# motor_driver.net
KiCad netlist of a schematic drawn in Altium Designer
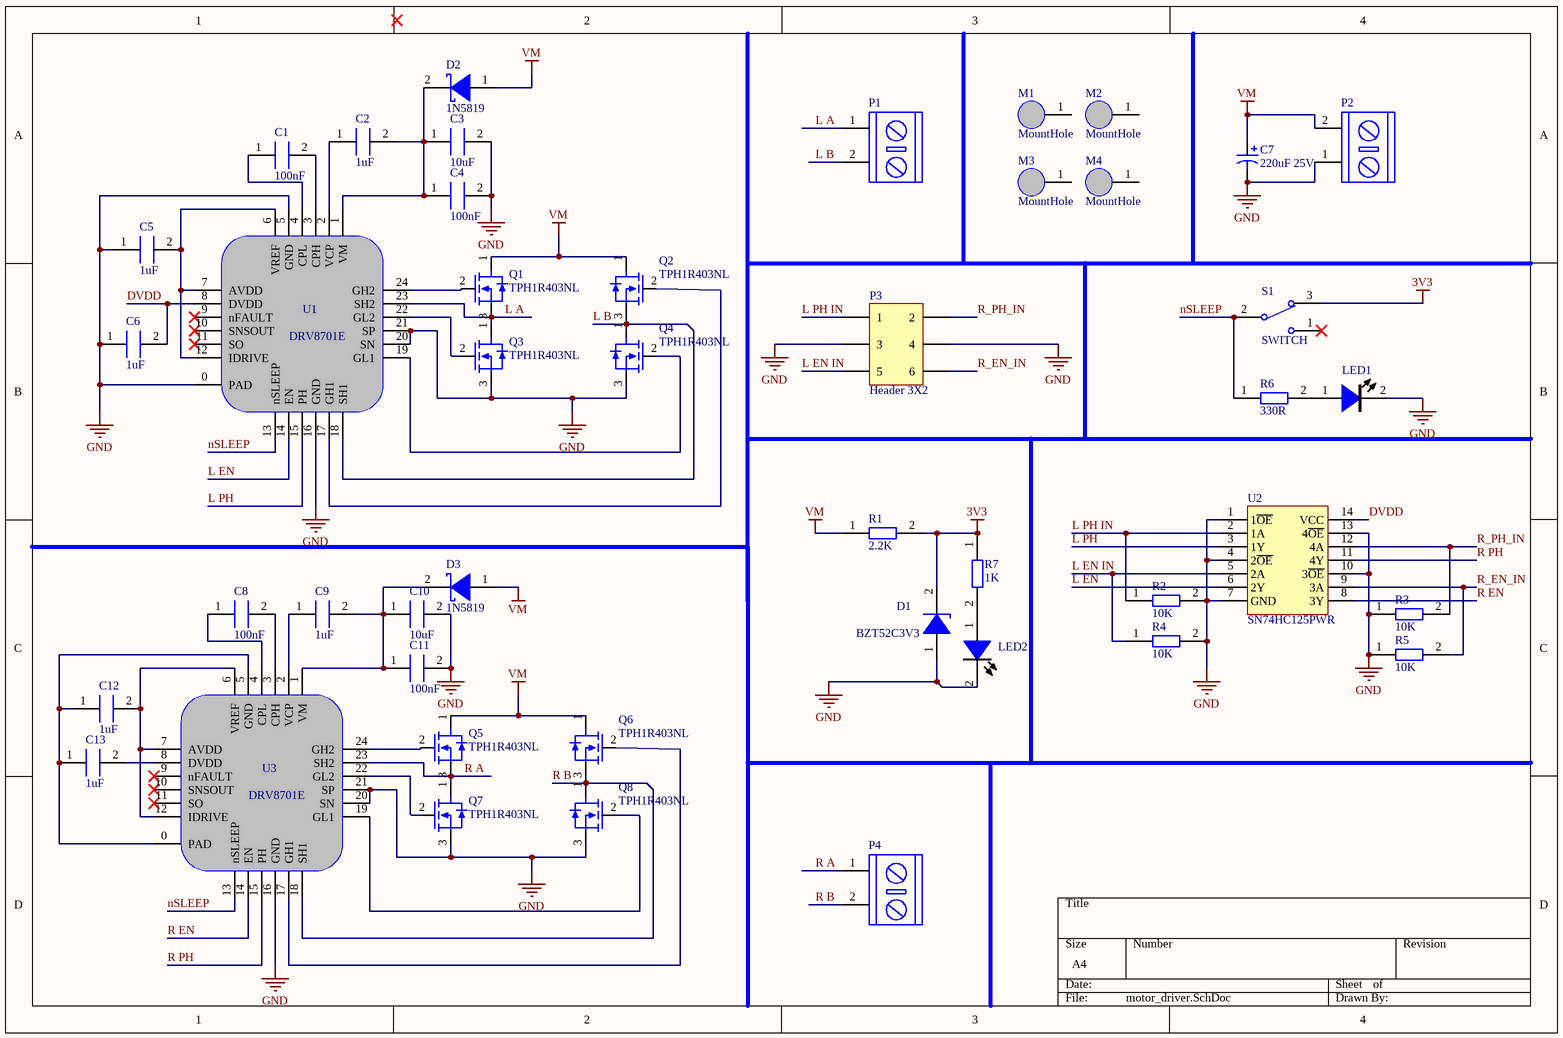
[diagram p0: motor_driver.SchDoc]

(export (version "E")
  (design (tool "Eeschema 10.0.6"))
  (components
    (comp (ref "C1")
      (value "100nF")
      (footprint "C0603")
      (description "电容")
      (libsource (lib "Learning") (part "CAP"))
    )
    (comp (ref "C2")
      (value "1uF")
      (footprint "C0603")
      (description "电容")
      (libsource (lib "Learning") (part "CAP"))
    )
    (comp (ref "C3")
      (value "10uF")
      (footprint "C0805")
      (description "电容")
      (libsource (lib "Learning") (part "CAP"))
    )
    (comp (ref "C4")
      (value "100nF")
      (footprint "C0603")
      (description "电容")
      (libsource (lib "Learning") (part "CAP"))
    )
    (comp (ref "C5")
      (value "1uF")
      (footprint "C0603")
      (description "电容")
      (libsource (lib "Learning") (part "CAP"))
    )
    (comp (ref "C6")
      (value "1uF")
      (footprint "C0603")
      (description "电容")
      (libsource (lib "Learning") (part "CAP"))
    )
    (comp (ref "C7") (value "220uF 25V") (footprint "RB.2/.4") (libsource (lib "Learning") (part "CAP_2")))
    (comp (ref "C8")
      (value "100nF")
      (footprint "C0603")
      (description "电容")
      (libsource (lib "Learning") (part "CAP"))
    )
    (comp (ref "C9")
      (value "1uF")
      (footprint "C0603")
      (description "电容")
      (libsource (lib "Learning") (part "CAP"))
    )
    (comp (ref "C10")
      (value "10uF")
      (footprint "C0805")
      (description "电容")
      (libsource (lib "Learning") (part "CAP"))
    )
    (comp (ref "C11")
      (value "100nF")
      (footprint "C0603")
      (description "电容")
      (libsource (lib "Learning") (part "CAP"))
    )
    (comp (ref "C12")
      (value "1uF")
      (footprint "C0603")
      (description "电容")
      (libsource (lib "Learning") (part "CAP"))
    )
    (comp (ref "C13")
      (value "1uF")
      (footprint "C0603")
      (description "电容")
      (libsource (lib "Learning") (part "CAP"))
    )
    (comp (ref "D1")
      (value "BZT52C3V3")
      (footprint "SOD-123")
      (libsource (lib "Learning") (part "BZT52C3V3"))
    )
    (comp (ref "D2") (value "1N5819") (footprint "SOD-123") (libsource (lib "Learning") (part "1N5819")))
    (comp (ref "D3") (value "1N5819") (footprint "SOD-123") (libsource (lib "Learning") (part "1N5819")))
    (comp (ref "LED1") (value "LED") (footprint "LED-0805") (libsource (lib "Learning") (part "LED")))
    (comp (ref "LED2") (value "LED") (footprint "LED-0805") (libsource (lib "Learning") (part "LED")))
    (comp (ref "M1")
      (value "MountHole")
      (footprint "MountHole")
      (libsource (lib "Learning") (part "MountHole"))
    )
    (comp (ref "M2")
      (value "MountHole")
      (footprint "MountHole")
      (libsource (lib "Learning") (part "MountHole"))
    )
    (comp (ref "M3")
      (value "MountHole")
      (footprint "MountHole")
      (libsource (lib "Learning") (part "MountHole"))
    )
    (comp (ref "M4")
      (value "MountHole")
      (footprint "MountHole")
      (libsource (lib "Learning") (part "MountHole"))
    )
    (comp (ref "P1")
      (value "接口_1")
      (footprint "KF/WJ/DG 301-2p-5.0mm")
      (libsource (lib "Learning") (part "接口_1"))
    )
    (comp (ref "P2")
      (value "接口")
      (footprint "KF/WJ/DG 301-2p-5.0mm")
      (libsource (lib "Learning") (part "接口"))
    )
    (comp (ref "P3")
      (value "Header 3X2")
      (footprint "PIN-2x3-2.54-1.0")
      (libsource (lib "Learning") (part "Header 3X2"))
    )
    (comp (ref "P4")
      (value "接口_1")
      (footprint "KF/WJ/DG 301-2p-5.0mm")
      (libsource (lib "Learning") (part "接口_1"))
    )
    (comp (ref "Q1")
      (value "TPH1R403NL")
      (footprint "DFN5x6")
      (description "MOSFET")
      (libsource (lib "Learning") (part "TPH1R403NL"))
    )
    (comp (ref "Q2")
      (value "TPH1R403NL")
      (footprint "DFN5x6")
      (description "MOSFET")
      (libsource (lib "Learning") (part "TPH1R403NL"))
    )
    (comp (ref "Q3")
      (value "TPH1R403NL")
      (footprint "DFN5x6")
      (description "MOSFET")
      (libsource (lib "Learning") (part "TPH1R403NL"))
    )
    (comp (ref "Q4")
      (value "TPH1R403NL")
      (footprint "DFN5x6")
      (description "MOSFET")
      (libsource (lib "Learning") (part "TPH1R403NL"))
    )
    (comp (ref "Q5")
      (value "TPH1R403NL")
      (footprint "DFN5x6")
      (description "MOSFET")
      (libsource (lib "Learning") (part "TPH1R403NL"))
    )
    (comp (ref "Q6")
      (value "TPH1R403NL")
      (footprint "DFN5x6")
      (description "MOSFET")
      (libsource (lib "Learning") (part "TPH1R403NL"))
    )
    (comp (ref "Q7")
      (value "TPH1R403NL")
      (footprint "DFN5x6")
      (description "MOSFET")
      (libsource (lib "Learning") (part "TPH1R403NL"))
    )
    (comp (ref "Q8")
      (value "TPH1R403NL")
      (footprint "DFN5x6")
      (description "MOSFET")
      (libsource (lib "Learning") (part "TPH1R403NL"))
    )
    (comp (ref "R1")
      (value "2.2K")
      (footprint "0603")
      (description "电阻")
      (libsource (lib "Learning") (part "RES"))
    )
    (comp (ref "R2")
      (value "10K")
      (footprint "0603")
      (description "电阻")
      (libsource (lib "Learning") (part "RES"))
    )
    (comp (ref "R3")
      (value "10K")
      (footprint "0603")
      (description "电阻")
      (libsource (lib "Learning") (part "RES"))
    )
    (comp (ref "R4")
      (value "10K")
      (footprint "0603")
      (description "电阻")
      (libsource (lib "Learning") (part "RES"))
    )
    (comp (ref "R5")
      (value "10K")
      (footprint "0603")
      (description "电阻")
      (libsource (lib "Learning") (part "RES"))
    )
    (comp (ref "R6")
      (value "330R")
      (footprint "0603")
      (description "电阻")
      (libsource (lib "Learning") (part "RES"))
    )
    (comp (ref "R7")
      (value "1K")
      (footprint "0603")
      (description "电阻")
      (libsource (lib "Learning") (part "RES"))
    )
    (comp (ref "S1")
      (value "SWITCH")
      (footprint "ToggleSwitch 7102")
      (libsource (lib "Learning") (part "SWITCH"))
    )
    (comp (ref "U1")
      (value "DRV8701E")
      (footprint "QFN24-4x4")
      (libsource (lib "Learning") (part "DRV8701E"))
    )
    (comp (ref "U2")
      (value "SN74HC125PWR")
      (footprint "TSSOP-14")
      (description "IC")
      (libsource (lib "Learning") (part "SN74HC125PWR"))
    )
    (comp (ref "U3")
      (value "DRV8701E")
      (footprint "QFN24-4x4")
      (libsource (lib "Learning") (part "DRV8701E"))
    )
  )
  (nets
    (net (code "1") (name "/DVDD") (class "Default")
      (node (ref "C6") (pin "2") (pinfunction "2_2") (pintype "passive"))
      (node (ref "U1") (pin "8") (pinfunction "DVDD_8") (pintype "passive"))
      (node (ref "U2") (pin "14") (pinfunction "VCC_14") (pintype "passive"))
    )
    (net (code "2") (name "/L A") (class "Default")
      (node (ref "P1") (pin "1") (pinfunction "31_1") (pintype "passive"))
      (node (ref "Q1") (pin "3") (pintype "passive"))
      (node (ref "Q3") (pin "1") (pintype "passive"))
      (node (ref "U1") (pin "23") (pinfunction "SH2_23") (pintype "passive"))
    )
    (net (code "3") (name "/L B") (class "Default")
      (node (ref "P1") (pin "2") (pinfunction "32_2") (pintype "passive"))
      (node (ref "Q2") (pin "3") (pintype "passive"))
      (node (ref "Q4") (pin "1") (pintype "passive"))
      (node (ref "U1") (pin "18") (pinfunction "SH1_18") (pintype "passive"))
    )
    (net (code "4") (name "/L EN") (class "Default")
      (node (ref "U1") (pin "14") (pinfunction "EN_14") (pintype "passive"))
      (node (ref "U2") (pin "6") (pinfunction "2Y_6") (pintype "passive"))
    )
    (net (code "5") (name "/L EN IN") (class "Default")
      (node (ref "P3") (pin "5") (pinfunction "5_5") (pintype "passive"))
      (node (ref "R4") (pin "1") (pinfunction "1_1") (pintype "passive"))
      (node (ref "U2") (pin "5") (pinfunction "2A_5") (pintype "passive"))
    )
    (net (code "6") (name "/L PH") (class "Default")
      (node (ref "U1") (pin "15") (pinfunction "PH_15") (pintype "passive"))
      (node (ref "U2") (pin "3") (pinfunction "1Y_3") (pintype "passive"))
    )
    (net (code "7") (name "/L PH IN") (class "Default")
      (node (ref "P3") (pin "1") (pinfunction "1_1") (pintype "passive"))
      (node (ref "R2") (pin "1") (pinfunction "1_1") (pintype "passive"))
      (node (ref "U2") (pin "2") (pinfunction "1A_2") (pintype "passive"))
    )
    (net (code "8") (name "/R A") (class "Default")
      (node (ref "P4") (pin "1") (pinfunction "31_1") (pintype "passive"))
      (node (ref "Q5") (pin "3") (pintype "passive"))
      (node (ref "Q7") (pin "1") (pintype "passive"))
      (node (ref "U3") (pin "23") (pinfunction "SH2_23") (pintype "passive"))
    )
    (net (code "9") (name "/R B") (class "Default")
      (node (ref "P4") (pin "2") (pinfunction "32_2") (pintype "passive"))
      (node (ref "Q6") (pin "3") (pintype "passive"))
      (node (ref "Q8") (pin "1") (pintype "passive"))
      (node (ref "U3") (pin "18") (pinfunction "SH1_18") (pintype "passive"))
    )
    (net (code "10") (name "/R EN") (class "Default")
      (node (ref "U2") (pin "8") (pinfunction "3Y_8") (pintype "passive"))
      (node (ref "U3") (pin "14") (pinfunction "EN_14") (pintype "passive"))
    )
    (net (code "11") (name "/R PH") (class "Default")
      (node (ref "U2") (pin "11") (pinfunction "4Y_11") (pintype "passive"))
      (node (ref "U3") (pin "15") (pinfunction "PH_15") (pintype "passive"))
    )
    (net (code "12") (name "/R_EN_IN") (class "Default")
      (node (ref "P3") (pin "6") (pinfunction "6_6") (pintype "passive"))
      (node (ref "R5") (pin "2") (pinfunction "2_2") (pintype "passive"))
      (node (ref "U2") (pin "9") (pinfunction "3A_9") (pintype "passive"))
    )
    (net (code "13") (name "/R_PH_IN") (class "Default")
      (node (ref "P3") (pin "2") (pinfunction "2_2") (pintype "passive"))
      (node (ref "R3") (pin "2") (pinfunction "2_2") (pintype "passive"))
      (node (ref "U2") (pin "12") (pinfunction "4A_12") (pintype "passive"))
    )
    (net (code "14") (name "/nSLEEP") (class "Default")
      (node (ref "R6") (pin "1") (pinfunction "1_1") (pintype "passive"))
      (node (ref "S1") (pin "2") (pinfunction "2_2") (pintype "passive"))
      (node (ref "U1") (pin "13") (pinfunction "nSLEEP_13") (pintype "passive"))
      (node (ref "U3") (pin "13") (pinfunction "nSLEEP_13") (pintype "passive"))
    )
    (net (code "15") (name "3V3") (class "Default")
      (node (ref "D1") (pin "2") (pinfunction "2_2") (pintype "passive"))
      (node (ref "R1") (pin "2") (pinfunction "2_2") (pintype "passive"))
      (node (ref "R7") (pin "1") (pinfunction "1_1") (pintype "passive"))
      (node (ref "S1") (pin "3") (pinfunction "3_3") (pintype "passive"))
    )
    (net (code "16") (name "GND") (class "Default")
      (node (ref "C10") (pin "2") (pinfunction "2_2") (pintype "passive"))
      (node (ref "C11") (pin "2") (pinfunction "2_2") (pintype "passive"))
      (node (ref "C3") (pin "2") (pinfunction "2_2") (pintype "passive"))
      (node (ref "C4") (pin "2") (pinfunction "2_2") (pintype "passive"))
      (node (ref "C5") (pin "1") (pinfunction "1_1") (pintype "passive"))
      (node (ref "C6") (pin "1") (pinfunction "1_1") (pintype "passive"))
      (node (ref "C7") (pin "2") (pinfunction "2_2") (pintype "passive"))
      (node (ref "D1") (pin "1") (pinfunction "1_1") (pintype "passive"))
      (node (ref "LED1") (pin "2") (pinfunction "2_2") (pintype "passive"))
      (node (ref "LED2") (pin "2") (pinfunction "2_2") (pintype "passive"))
      (node (ref "P2") (pin "1") (pinfunction "32_1") (pintype "passive"))
      (node (ref "P3") (pin "3") (pinfunction "3_3") (pintype "passive"))
      (node (ref "P3") (pin "4") (pinfunction "4_4") (pintype "passive"))
      (node (ref "Q3") (pin "3") (pintype "passive"))
      (node (ref "Q4") (pin "3") (pintype "passive"))
      (node (ref "Q7") (pin "3") (pintype "passive"))
      (node (ref "Q8") (pin "3") (pintype "passive"))
      (node (ref "R2") (pin "2") (pinfunction "2_2") (pintype "passive"))
      (node (ref "R3") (pin "1") (pinfunction "1_1") (pintype "passive"))
      (node (ref "R4") (pin "2") (pinfunction "2_2") (pintype "passive"))
      (node (ref "R5") (pin "1") (pinfunction "1_1") (pintype "passive"))
      (node (ref "U1") (pin "0") (pinfunction "PAD_0") (pintype "passive"))
      (node (ref "U1") (pin "16") (pinfunction "GND_16") (pintype "passive"))
      (node (ref "U1") (pin "20") (pinfunction "SN_20") (pintype "passive"))
      (node (ref "U1") (pin "21") (pinfunction "SP_21") (pintype "passive"))
      (node (ref "U1") (pin "5") (pinfunction "GND_5") (pintype "passive"))
      (node (ref "U2") (pin "1") (pinfunction "1~{OE}_1") (pintype "passive"))
      (node (ref "U2") (pin "10") (pinfunction "3~{OE}_10") (pintype "passive"))
      (node (ref "U2") (pin "13") (pinfunction "4~{OE}_13") (pintype "passive"))
      (node (ref "U2") (pin "4") (pinfunction "2~{OE}_4") (pintype "passive"))
      (node (ref "U2") (pin "7") (pinfunction "GND_7") (pintype "passive"))
      (node (ref "U3") (pin "16") (pinfunction "GND_16") (pintype "passive"))
      (node (ref "U3") (pin "20") (pinfunction "SN_20") (pintype "passive"))
      (node (ref "U3") (pin "21") (pinfunction "SP_21") (pintype "passive"))
    )
    (net (code "17") (name "Net-(LED1-Pad1)") (class "Default")
      (node (ref "LED1") (pin "1") (pinfunction "1_1") (pintype "passive"))
      (node (ref "R6") (pin "2") (pinfunction "2_2") (pintype "passive"))
    )
    (net (code "18") (name "Net-(LED2-Pad1)") (class "Default")
      (node (ref "LED2") (pin "1") (pinfunction "1_1") (pintype "passive"))
      (node (ref "R7") (pin "2") (pinfunction "2_2") (pintype "passive"))
    )
    (net (code "19") (name "Net-(U1-AVDD)") (class "Default")
      (node (ref "C5") (pin "2") (pinfunction "2_2") (pintype "passive"))
      (node (ref "U1") (pin "12") (pinfunction "IDRIVE_12") (pintype "passive"))
      (node (ref "U1") (pin "6") (pinfunction "VREF_6") (pintype "passive"))
      (node (ref "U1") (pin "7") (pinfunction "AVDD_7") (pintype "passive"))
    )
    (net (code "20") (name "Net-(U1-CPH)") (class "Default")
      (node (ref "C1") (pin "2") (pinfunction "2_2") (pintype "passive"))
      (node (ref "U1") (pin "3") (pinfunction "CPH_3") (pintype "passive"))
    )
    (net (code "21") (name "Net-(U1-CPL)") (class "Default")
      (node (ref "C1") (pin "1") (pinfunction "1_1") (pintype "passive"))
      (node (ref "U1") (pin "4") (pinfunction "CPL_4") (pintype "passive"))
    )
    (net (code "22") (name "Net-(U1-GH1)") (class "Default")
      (node (ref "Q2") (pin "2") (pintype "passive"))
      (node (ref "U1") (pin "17") (pinfunction "GH1_17") (pintype "passive"))
    )
    (net (code "23") (name "Net-(U1-GH2)") (class "Default")
      (node (ref "Q1") (pin "2") (pintype "passive"))
      (node (ref "U1") (pin "24") (pinfunction "GH2_24") (pintype "passive"))
    )
    (net (code "24") (name "Net-(U1-GL1)") (class "Default")
      (node (ref "Q4") (pin "2") (pintype "passive"))
      (node (ref "U1") (pin "19") (pinfunction "GL1_19") (pintype "passive"))
    )
    (net (code "25") (name "Net-(U1-GL2)") (class "Default")
      (node (ref "Q3") (pin "2") (pintype "passive"))
      (node (ref "U1") (pin "22") (pinfunction "GL2_22") (pintype "passive"))
    )
    (net (code "26") (name "Net-(U1-VCP)") (class "Default")
      (node (ref "C2") (pin "1") (pinfunction "1_1") (pintype "passive"))
      (node (ref "U1") (pin "2") (pinfunction "VCP_2") (pintype "passive"))
    )
    (net (code "27") (name "Net-(U1-VM)") (class "Default")
      (node (ref "C2") (pin "2") (pinfunction "2_2") (pintype "passive"))
      (node (ref "C3") (pin "1") (pinfunction "1_1") (pintype "passive"))
      (node (ref "C4") (pin "1") (pinfunction "1_1") (pintype "passive"))
      (node (ref "D2") (pin "2") (pinfunction "2_2") (pintype "passive"))
      (node (ref "U1") (pin "1") (pinfunction "VM_1") (pintype "passive"))
    )
    (net (code "28") (name "Net-(U3-AVDD)") (class "Default")
      (node (ref "C12") (pin "2") (pinfunction "2_2") (pintype "passive"))
      (node (ref "U3") (pin "12") (pinfunction "IDRIVE_12") (pintype "passive"))
      (node (ref "U3") (pin "6") (pinfunction "VREF_6") (pintype "passive"))
      (node (ref "U3") (pin "7") (pinfunction "AVDD_7") (pintype "passive"))
    )
    (net (code "29") (name "Net-(U3-CPH)") (class "Default")
      (node (ref "C8") (pin "2") (pinfunction "2_2") (pintype "passive"))
      (node (ref "U3") (pin "3") (pinfunction "CPH_3") (pintype "passive"))
    )
    (net (code "30") (name "Net-(U3-CPL)") (class "Default")
      (node (ref "C8") (pin "1") (pinfunction "1_1") (pintype "passive"))
      (node (ref "U3") (pin "4") (pinfunction "CPL_4") (pintype "passive"))
    )
    (net (code "31") (name "Net-(U3-DVDD)") (class "Default")
      (node (ref "C13") (pin "2") (pinfunction "2_2") (pintype "passive"))
      (node (ref "U3") (pin "8") (pinfunction "DVDD_8") (pintype "passive"))
    )
    (net (code "32") (name "Net-(U3-GH1)") (class "Default")
      (node (ref "Q6") (pin "2") (pintype "passive"))
      (node (ref "U3") (pin "17") (pinfunction "GH1_17") (pintype "passive"))
    )
    (net (code "33") (name "Net-(U3-GH2)") (class "Default")
      (node (ref "Q5") (pin "2") (pintype "passive"))
      (node (ref "U3") (pin "24") (pinfunction "GH2_24") (pintype "passive"))
    )
    (net (code "34") (name "Net-(U3-GL1)") (class "Default")
      (node (ref "Q8") (pin "2") (pintype "passive"))
      (node (ref "U3") (pin "19") (pinfunction "GL1_19") (pintype "passive"))
    )
    (net (code "35") (name "Net-(U3-GL2)") (class "Default")
      (node (ref "Q7") (pin "2") (pintype "passive"))
      (node (ref "U3") (pin "22") (pinfunction "GL2_22") (pintype "passive"))
    )
    (net (code "36") (name "Net-(U3-PAD)") (class "Default")
      (node (ref "C12") (pin "1") (pinfunction "1_1") (pintype "passive"))
      (node (ref "C13") (pin "1") (pinfunction "1_1") (pintype "passive"))
      (node (ref "U3") (pin "0") (pinfunction "PAD_0") (pintype "passive"))
      (node (ref "U3") (pin "5") (pinfunction "GND_5") (pintype "passive"))
    )
    (net (code "37") (name "Net-(U3-VCP)") (class "Default")
      (node (ref "C9") (pin "1") (pinfunction "1_1") (pintype "passive"))
      (node (ref "U3") (pin "2") (pinfunction "VCP_2") (pintype "passive"))
    )
    (net (code "38") (name "Net-(U3-VM)") (class "Default")
      (node (ref "C10") (pin "1") (pinfunction "1_1") (pintype "passive"))
      (node (ref "C11") (pin "1") (pinfunction "1_1") (pintype "passive"))
      (node (ref "C9") (pin "2") (pinfunction "2_2") (pintype "passive"))
      (node (ref "D3") (pin "2") (pinfunction "2_2") (pintype "passive"))
      (node (ref "U3") (pin "1") (pinfunction "VM_1") (pintype "passive"))
    )
    (net (code "39") (name "VM") (class "Default")
      (node (ref "C7") (pin "1") (pinfunction "1_1") (pintype "passive"))
      (node (ref "D2") (pin "1") (pinfunction "1_1") (pintype "passive"))
      (node (ref "D3") (pin "1") (pinfunction "1_1") (pintype "passive"))
      (node (ref "P2") (pin "2") (pinfunction "31_2") (pintype "passive"))
      (node (ref "Q1") (pin "1") (pintype "passive"))
      (node (ref "Q2") (pin "1") (pintype "passive"))
      (node (ref "Q5") (pin "1") (pintype "passive"))
      (node (ref "Q6") (pin "1") (pintype "passive"))
      (node (ref "R1") (pin "1") (pinfunction "1_1") (pintype "passive"))
    )
    (net (code "40") (name "unconnected-(M1-Pad1)") (class "Default")
      (node (ref "M1") (pin "1") (pinfunction "1_1") (pintype "passive"))
    )
    (net (code "41") (name "unconnected-(M2-Pad1)") (class "Default")
      (node (ref "M2") (pin "1") (pinfunction "1_1") (pintype "passive"))
    )
    (net (code "42") (name "unconnected-(M3-Pad1)") (class "Default")
      (node (ref "M3") (pin "1") (pinfunction "1_1") (pintype "passive"))
    )
    (net (code "43") (name "unconnected-(M4-Pad1)") (class "Default")
      (node (ref "M4") (pin "1") (pinfunction "1_1") (pintype "passive"))
    )
    (net (code "44") (name "unconnected-(S1-Pad1)") (class "Default")
      (node (ref "S1") (pin "1") (pinfunction "1_1") (pintype "passive+no_connect"))
    )
    (net (code "45") (name "unconnected-(U1-SNSOUT-Pad10)") (class "Default")
      (node (ref "U1") (pin "10") (pinfunction "SNSOUT_10") (pintype "passive+no_connect"))
    )
    (net (code "46") (name "unconnected-(U1-SO-Pad11)") (class "Default")
      (node (ref "U1") (pin "11") (pinfunction "SO_11") (pintype "passive+no_connect"))
    )
    (net (code "47") (name "unconnected-(U1-nFAULT-Pad9)") (class "Default")
      (node (ref "U1") (pin "9") (pinfunction "nFAULT_9") (pintype "passive+no_connect"))
    )
    (net (code "48") (name "unconnected-(U3-SNSOUT-Pad10)") (class "Default")
      (node (ref "U3") (pin "10") (pinfunction "SNSOUT_10") (pintype "passive+no_connect"))
    )
    (net (code "49") (name "unconnected-(U3-SO-Pad11)") (class "Default")
      (node (ref "U3") (pin "11") (pinfunction "SO_11") (pintype "passive+no_connect"))
    )
    (net (code "50") (name "unconnected-(U3-nFAULT-Pad9)") (class "Default")
      (node (ref "U3") (pin "9") (pinfunction "nFAULT_9") (pintype "passive+no_connect"))
    )
  )
)
